# X1.net
KiCad netlist of a schematic drawn in Altium Designer
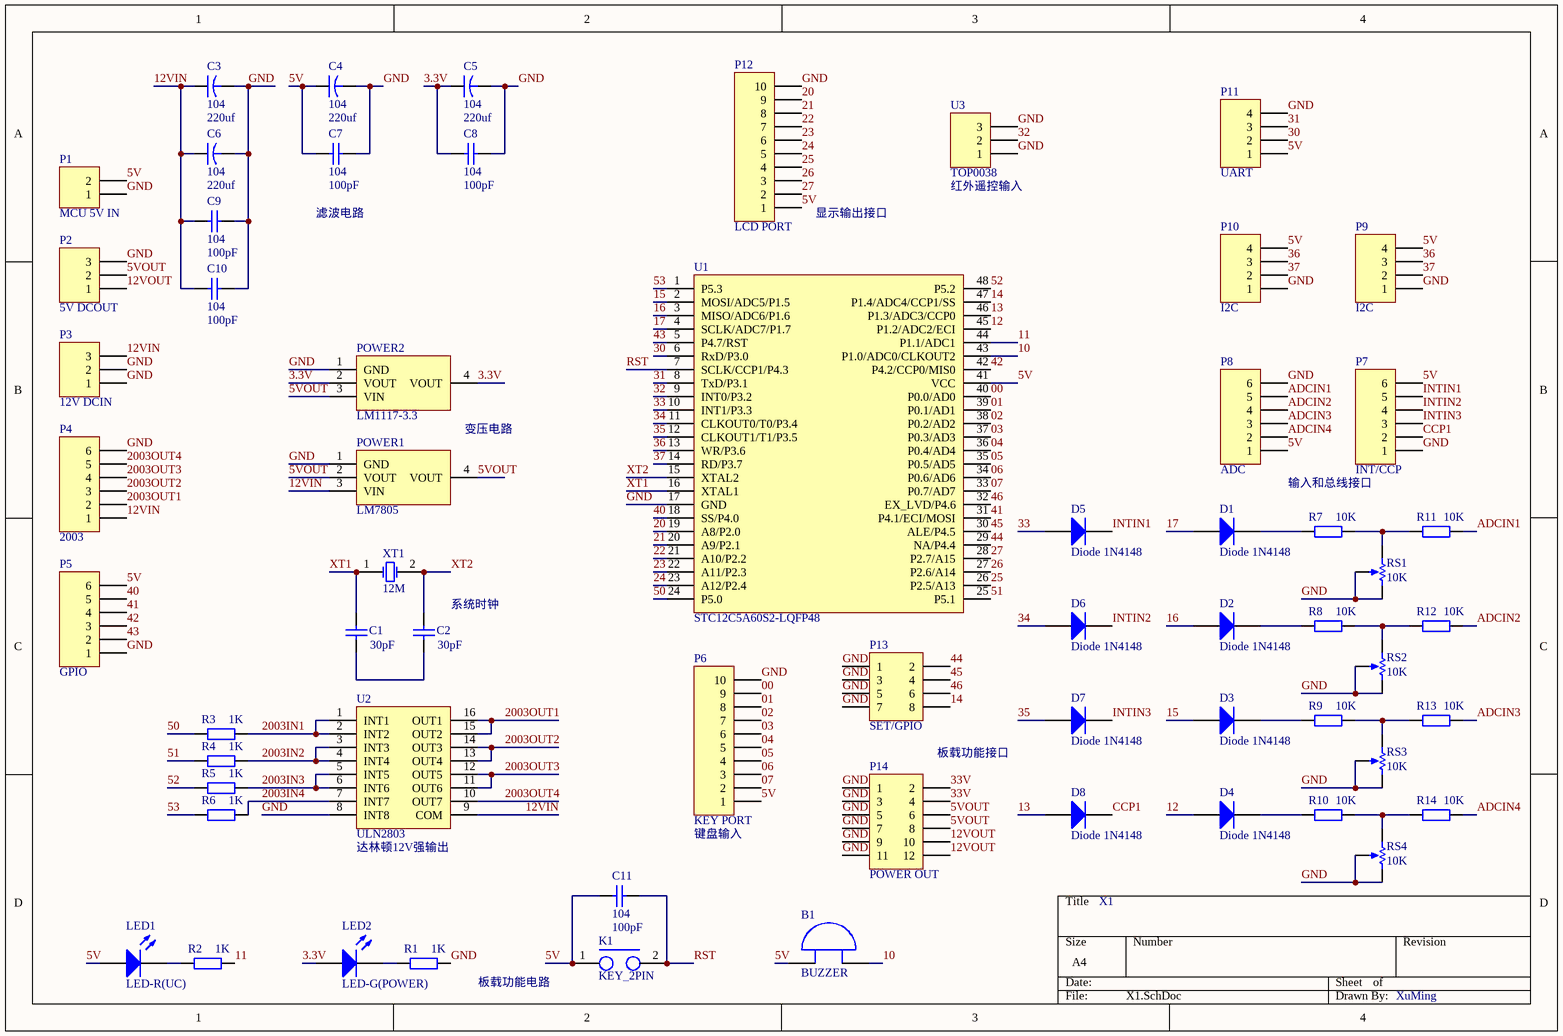
[diagram p0: X1.SchDoc]

(export (version "E")
  (design (tool "Eeschema 10.0.6"))
  (components
    (comp (ref "B1") (value "BUZZER") (footprint "BEEP1") (libsource (lib "X1") (part "BUZZER")))
    (comp (ref "C1")
      (value "30pF")
      (footprint "0805")
      (description "Capacitor")
      (fields (field (name "Comment") "Cap") (field (name "PUBLISHER") "Altium Limited"))
      (libsource (lib "Miscellaneous Devices") (part "Cap"))
    )
    (comp (ref "C2")
      (value "30pF")
      (footprint "0805")
      (description "Capacitor")
      (fields (field (name "Comment") "Cap") (field (name "PUBLISHER") "Altium Limited"))
      (libsource (lib "Miscellaneous Devices") (part "Cap"))
    )
    (comp (ref "C3")
      (value "104")
      (footprint "C107V")
      (description "Capacitor")
      (fields (field (name "ALTIUM_VALUE") "220uf") (field (name "PUBLISHER") "Altium Limited"))
      (libsource (lib "Miscellaneous Devices") (part "Cap2"))
    )
    (comp (ref "C4")
      (value "104")
      (footprint "C107V")
      (description "Capacitor")
      (fields (field (name "ALTIUM_VALUE") "220uf") (field (name "PUBLISHER") "Altium Limited"))
      (libsource (lib "Miscellaneous Devices") (part "Cap2"))
    )
    (comp (ref "C5")
      (value "104")
      (footprint "C107V")
      (description "Capacitor")
      (fields (field (name "ALTIUM_VALUE") "220uf") (field (name "PUBLISHER") "Altium Limited"))
      (libsource (lib "Miscellaneous Devices") (part "Cap2"))
    )
    (comp (ref "C6")
      (value "104")
      (footprint "C107V")
      (description "Capacitor")
      (fields (field (name "ALTIUM_VALUE") "220uf") (field (name "PUBLISHER") "Altium Limited"))
      (libsource (lib "Miscellaneous Devices") (part "Cap2"))
    )
    (comp (ref "C7")
      (value "104")
      (footprint "0805")
      (description "Capacitor")
      (fields (field (name "ALTIUM_VALUE") "100pF") (field (name "PUBLISHER") "Altium Limited"))
      (libsource (lib "Miscellaneous Devices") (part "Cap"))
    )
    (comp (ref "C8")
      (value "104")
      (footprint "0805")
      (description "Capacitor")
      (fields (field (name "ALTIUM_VALUE") "100pF") (field (name "PUBLISHER") "Altium Limited"))
      (libsource (lib "Miscellaneous Devices") (part "Cap"))
    )
    (comp (ref "C9")
      (value "104")
      (footprint "0805")
      (description "Capacitor")
      (fields (field (name "ALTIUM_VALUE") "100pF") (field (name "PUBLISHER") "Altium Limited"))
      (libsource (lib "Miscellaneous Devices") (part "Cap"))
    )
    (comp (ref "C10")
      (value "104")
      (footprint "0805")
      (description "Capacitor")
      (fields (field (name "ALTIUM_VALUE") "100pF") (field (name "PUBLISHER") "Altium Limited"))
      (libsource (lib "Miscellaneous Devices") (part "Cap"))
    )
    (comp (ref "C11")
      (value "104")
      (footprint "0805")
      (description "Capacitor")
      (fields (field (name "ALTIUM_VALUE") "100pF") (field (name "PUBLISHER") "Altium Limited"))
      (libsource (lib "Miscellaneous Devices") (part "Cap"))
    )
    (comp (ref "D1")
      (value "Diode 1N4148")
      (footprint "0805")
      (description "High Conductance Fast Diode")
      (fields (field (name "PUBLISHER") "Altium Limited"))
      (libsource (lib "Miscellaneous Devices") (part "Diode 1N4148"))
    )
    (comp (ref "D2")
      (value "Diode 1N4148")
      (footprint "0805")
      (description "High Conductance Fast Diode")
      (fields (field (name "PUBLISHER") "Altium Limited"))
      (libsource (lib "Miscellaneous Devices") (part "Diode 1N4148"))
    )
    (comp (ref "D3")
      (value "Diode 1N4148")
      (footprint "0805")
      (description "High Conductance Fast Diode")
      (fields (field (name "PUBLISHER") "Altium Limited"))
      (libsource (lib "Miscellaneous Devices") (part "Diode 1N4148"))
    )
    (comp (ref "D4")
      (value "Diode 1N4148")
      (footprint "0805")
      (description "High Conductance Fast Diode")
      (fields (field (name "PUBLISHER") "Altium Limited"))
      (libsource (lib "Miscellaneous Devices") (part "Diode 1N4148"))
    )
    (comp (ref "D5")
      (value "Diode 1N4148")
      (footprint "0805")
      (description "High Conductance Fast Diode")
      (fields (field (name "PUBLISHER") "Altium Limited"))
      (libsource (lib "Miscellaneous Devices") (part "Diode 1N4148"))
    )
    (comp (ref "D6")
      (value "Diode 1N4148")
      (footprint "0805")
      (description "High Conductance Fast Diode")
      (fields (field (name "PUBLISHER") "Altium Limited"))
      (libsource (lib "Miscellaneous Devices") (part "Diode 1N4148"))
    )
    (comp (ref "D7")
      (value "Diode 1N4148")
      (footprint "0805")
      (description "High Conductance Fast Diode")
      (fields (field (name "PUBLISHER") "Altium Limited"))
      (libsource (lib "Miscellaneous Devices") (part "Diode 1N4148"))
    )
    (comp (ref "D8")
      (value "Diode 1N4148")
      (footprint "0805")
      (description "High Conductance Fast Diode")
      (fields (field (name "PUBLISHER") "Altium Limited"))
      (libsource (lib "Miscellaneous Devices") (part "Diode 1N4148"))
    )
    (comp (ref "K1") (value "KEY_2PIN") (footprint "KEY-4Pin") (libsource (lib "X1") (part "KEY_2PIN")))
    (comp (ref "LED1")
      (value "LED-R(UC)")
      (footprint "0805")
      (description "Typical RED, GREEN, YELLOW, AMBER GaAs LED")
      (fields (field (name "PUBLISHER") "Altium Limited"))
      (libsource (lib "Miscellaneous Devices") (part "LED2"))
    )
    (comp (ref "LED2")
      (value "LED-G(POWER)")
      (footprint "0805")
      (description "Typical RED, GREEN, YELLOW, AMBER GaAs LED")
      (fields (field (name "PUBLISHER") "Altium Limited"))
      (libsource (lib "Miscellaneous Devices") (part "LED2"))
    )
    (comp (ref "P1")
      (value "MCU 5V IN")
      (footprint "HDR1X2")
      (description "Header, 2-Pin")
      (fields (field (name "PUBLISHER") "Altium Limited"))
      (libsource (lib "Miscellaneous Connectors") (part "Header 2"))
    )
    (comp (ref "P2")
      (value "5V DCOUT")
      (footprint "HDR1X3")
      (description "Header, 3-Pin")
      (fields (field (name "PUBLISHER") "Altium Limited"))
      (libsource (lib "Miscellaneous Connectors") (part "Header 3"))
    )
    (comp (ref "P3")
      (value "12V DCIN")
      (footprint "HDR1X3")
      (description "Header, 3-Pin")
      (fields (field (name "PUBLISHER") "Altium Limited"))
      (libsource (lib "Miscellaneous Connectors") (part "Header 3"))
    )
    (comp (ref "P4")
      (value "2003")
      (footprint "HDR1X6")
      (description "Header, 6-Pin")
      (fields (field (name "PUBLISHER") "Altium Limited"))
      (libsource (lib "Miscellaneous Connectors") (part "Header 6"))
    )
    (comp (ref "P5")
      (value "GPIO")
      (footprint "HDR1X6")
      (description "Header, 6-Pin")
      (fields (field (name "PUBLISHER") "Altium Limited"))
      (libsource (lib "Miscellaneous Connectors") (part "Header 6"))
    )
    (comp (ref "P6")
      (value "KEY PORT")
      (footprint "HDR1X10")
      (description "Header, 10-Pin")
      (fields (field (name "PUBLISHER") "Altium Limited"))
      (libsource (lib "Miscellaneous Connectors") (part "Header 10"))
    )
    (comp (ref "P7")
      (value "INT/CCP")
      (footprint "HDR1X6")
      (description "Header, 6-Pin")
      (fields (field (name "PUBLISHER") "Altium Limited"))
      (libsource (lib "Miscellaneous Connectors") (part "Header 6"))
    )
    (comp (ref "P8")
      (value "ADC")
      (footprint "HDR1X6")
      (description "Header, 6-Pin")
      (fields (field (name "PUBLISHER") "Altium Limited"))
      (libsource (lib "Miscellaneous Connectors") (part "Header 6"))
    )
    (comp (ref "P9")
      (value "I2C")
      (footprint "HDR1X4")
      (description "Header, 4-Pin")
      (fields (field (name "PUBLISHER") "Altium Limited"))
      (libsource (lib "Miscellaneous Connectors") (part "Header 4"))
    )
    (comp (ref "P10")
      (value "I2C")
      (footprint "HDR1X4")
      (description "Header, 4-Pin")
      (fields (field (name "PUBLISHER") "Altium Limited"))
      (libsource (lib "Miscellaneous Connectors") (part "Header 4"))
    )
    (comp (ref "P11")
      (value "UART")
      (footprint "HDR1X4")
      (description "Header, 4-Pin")
      (fields (field (name "PUBLISHER") "Altium Limited"))
      (libsource (lib "Miscellaneous Connectors") (part "Header 4"))
    )
    (comp (ref "P12")
      (value "LCD PORT")
      (footprint "HDR1X10")
      (description "Header, 10-Pin")
      (fields (field (name "PUBLISHER") "Altium Limited"))
      (libsource (lib "Miscellaneous Connectors") (part "Header 10"))
    )
    (comp (ref "P13")
      (value "SET/GPIO")
      (footprint "HDR2X4")
      (description "Header, 4-Pin, Dual row")
      (fields (field (name "PUBLISHER") "Altium Limited"))
      (libsource (lib "Miscellaneous Connectors") (part "Header 4X2"))
    )
    (comp (ref "P14")
      (value "POWER OUT")
      (footprint "HDR2X6")
      (description "Header, 6-Pin, Dual row")
      (fields (field (name "PUBLISHER") "Altium Limited"))
      (libsource (lib "Miscellaneous Connectors") (part "Header 6X2"))
    )
    (comp (ref "POWER1") (value "LM7805") (footprint "SOT223_N") (libsource (lib "X1") (part "LM7805")))
    (comp (ref "POWER2") (value "LM1117-3.3") (footprint "SOT223_N") (libsource (lib "X1") (part "LM7805")))
    (comp (ref "R1")
      (value "1K")
      (footprint "0805")
      (description "Resistor")
      (fields (field (name "Comment") "Res2") (field (name "PUBLISHER") "Altium Limited"))
      (libsource (lib "Miscellaneous Devices") (part "Res2"))
    )
    (comp (ref "R2")
      (value "1K")
      (footprint "0805")
      (description "Resistor")
      (fields (field (name "Comment") "Res2") (field (name "PUBLISHER") "Altium Limited"))
      (libsource (lib "Miscellaneous Devices") (part "Res2"))
    )
    (comp (ref "R3")
      (value "1K")
      (footprint "0805")
      (description "Resistor")
      (fields (field (name "Comment") "Res2") (field (name "PUBLISHER") "Altium Limited"))
      (libsource (lib "Miscellaneous Devices") (part "Res2"))
    )
    (comp (ref "R4")
      (value "1K")
      (footprint "0805")
      (description "Resistor")
      (fields (field (name "Comment") "Res2") (field (name "PUBLISHER") "Altium Limited"))
      (libsource (lib "Miscellaneous Devices") (part "Res2"))
    )
    (comp (ref "R5")
      (value "1K")
      (footprint "0805")
      (description "Resistor")
      (fields (field (name "Comment") "Res2") (field (name "PUBLISHER") "Altium Limited"))
      (libsource (lib "Miscellaneous Devices") (part "Res2"))
    )
    (comp (ref "R6")
      (value "1K")
      (footprint "0805")
      (description "Resistor")
      (fields (field (name "Comment") "Res2") (field (name "PUBLISHER") "Altium Limited"))
      (libsource (lib "Miscellaneous Devices") (part "Res2"))
    )
    (comp (ref "R7")
      (value "10K")
      (footprint "0805")
      (description "Resistor")
      (fields (field (name "Comment") "Res2") (field (name "PUBLISHER") "Altium Limited"))
      (libsource (lib "Miscellaneous Devices") (part "Res2"))
    )
    (comp (ref "R8")
      (value "10K")
      (footprint "0805")
      (description "Resistor")
      (fields (field (name "Comment") "Res2") (field (name "PUBLISHER") "Altium Limited"))
      (libsource (lib "Miscellaneous Devices") (part "Res2"))
    )
    (comp (ref "R9")
      (value "10K")
      (footprint "0805")
      (description "Resistor")
      (fields (field (name "Comment") "Res2") (field (name "PUBLISHER") "Altium Limited"))
      (libsource (lib "Miscellaneous Devices") (part "Res2"))
    )
    (comp (ref "R10")
      (value "10K")
      (footprint "0805")
      (description "Resistor")
      (fields (field (name "Comment") "Res2") (field (name "PUBLISHER") "Altium Limited"))
      (libsource (lib "Miscellaneous Devices") (part "Res2"))
    )
    (comp (ref "R11")
      (value "10K")
      (footprint "0805")
      (description "Resistor")
      (fields (field (name "Comment") "Res2") (field (name "PUBLISHER") "Altium Limited"))
      (libsource (lib "Miscellaneous Devices") (part "Res2"))
    )
    (comp (ref "R12")
      (value "10K")
      (footprint "0805")
      (description "Resistor")
      (fields (field (name "Comment") "Res2") (field (name "PUBLISHER") "Altium Limited"))
      (libsource (lib "Miscellaneous Devices") (part "Res2"))
    )
    (comp (ref "R13")
      (value "10K")
      (footprint "0805")
      (description "Resistor")
      (fields (field (name "Comment") "Res2") (field (name "PUBLISHER") "Altium Limited"))
      (libsource (lib "Miscellaneous Devices") (part "Res2"))
    )
    (comp (ref "R14")
      (value "10K")
      (footprint "0805")
      (description "Resistor")
      (fields (field (name "Comment") "Res2") (field (name "PUBLISHER") "Altium Limited"))
      (libsource (lib "Miscellaneous Devices") (part "Res2"))
    )
    (comp (ref "RS1")
      (value "10K")
      (footprint "VR5")
      (description "Potentiometer")
      (fields (field (name "Comment") "RPot") (field (name "PUBLISHER") "Altium Limited"))
      (libsource (lib "Miscellaneous Devices") (part "RPot"))
    )
    (comp (ref "RS2")
      (value "10K")
      (footprint "VR5")
      (description "Potentiometer")
      (fields (field (name "Comment") "RPot") (field (name "PUBLISHER") "Altium Limited"))
      (libsource (lib "Miscellaneous Devices") (part "RPot"))
    )
    (comp (ref "RS3")
      (value "10K")
      (footprint "VR5")
      (description "Potentiometer")
      (fields (field (name "Comment") "RPot") (field (name "PUBLISHER") "Altium Limited"))
      (libsource (lib "Miscellaneous Devices") (part "RPot"))
    )
    (comp (ref "RS4")
      (value "10K")
      (footprint "VR5")
      (description "Potentiometer")
      (fields (field (name "Comment") "RPot") (field (name "PUBLISHER") "Altium Limited"))
      (libsource (lib "Miscellaneous Devices") (part "RPot"))
    )
    (comp (ref "U1")
      (value "STC12C5A60S2-LQFP48")
      (footprint "LQFP-48_7x7x05P")
      (libsource (lib "X1") (part "STC12C5A60S2-LQFP48"))
    )
    (comp (ref "U2") (value "ULN2803") (footprint "SOP-16") (libsource (lib "Schlib1") (part "ULN2003")))
    (comp (ref "U3")
      (value "TOP0038")
      (footprint "HDR1X3")
      (description "Header, 3-Pin")
      (fields (field (name "PUBLISHER") "Altium Limited"))
      (libsource (lib "Miscellaneous Connectors") (part "Header 3"))
    )
    (comp (ref "XT1")
      (value "12M")
      (footprint "R38")
      (description "Crystal Oscillator")
      (fields (field (name "PUBLISHER") "Altium Limited"))
      (libsource (lib "Miscellaneous Devices") (part "XTAL"))
    )
  )
  (nets
    (net (code "1") (name "/00") (class "Default")
      (node (ref "P6") (pin "9") (pinfunction "9_9") (pintype "passive"))
      (node (ref "U1") (pin "40") (pinfunction "P0.0/AD0_40") (pintype "passive"))
    )
    (net (code "2") (name "/01") (class "Default")
      (node (ref "P6") (pin "8") (pinfunction "8_8") (pintype "passive"))
      (node (ref "U1") (pin "39") (pinfunction "P0.1/AD1_39") (pintype "passive"))
    )
    (net (code "3") (name "/02") (class "Default")
      (node (ref "P6") (pin "7") (pinfunction "7_7") (pintype "passive"))
      (node (ref "U1") (pin "38") (pinfunction "P0.2/AD2_38") (pintype "passive"))
    )
    (net (code "4") (name "/03") (class "Default")
      (node (ref "P6") (pin "6") (pinfunction "6_6") (pintype "passive"))
      (node (ref "U1") (pin "37") (pinfunction "P0.3/AD3_37") (pintype "passive"))
    )
    (net (code "5") (name "/3.3V") (class "Default")
      (node (ref "C5") (pin "1") (pinfunction "1_1") (pintype "passive"))
      (node (ref "C8") (pin "1") (pinfunction "1_1") (pintype "passive"))
      (node (ref "LED2") (pin "1") (pinfunction "A_1") (pintype "passive"))
      (node (ref "POWER2") (pin "2") (pinfunction "VOUT_2") (pintype "passive"))
      (node (ref "POWER2") (pin "4") (pinfunction "VOUT_4") (pintype "passive"))
    )
    (net (code "6") (name "/04") (class "Default")
      (node (ref "P6") (pin "5") (pinfunction "5_5") (pintype "passive"))
      (node (ref "U1") (pin "36") (pinfunction "P0.4/AD4_36") (pintype "passive"))
    )
    (net (code "7") (name "/05") (class "Default")
      (node (ref "P6") (pin "4") (pinfunction "4_4") (pintype "passive"))
      (node (ref "U1") (pin "35") (pinfunction "P0.5/AD5_35") (pintype "passive"))
    )
    (net (code "8") (name "/5V") (class "Default")
      (node (ref "B1") (pin "1") (pinfunction "1_1") (pintype "passive"))
      (node (ref "C11") (pin "1") (pinfunction "1_1") (pintype "passive"))
      (node (ref "C4") (pin "1") (pinfunction "1_1") (pintype "passive"))
      (node (ref "C7") (pin "1") (pinfunction "1_1") (pintype "passive"))
      (node (ref "K1") (pin "1") (pinfunction "1_1") (pintype "passive"))
      (node (ref "LED1") (pin "1") (pinfunction "A_1") (pintype "passive"))
      (node (ref "P1") (pin "2") (pinfunction "2_2") (pintype "passive"))
      (node (ref "P10") (pin "4") (pinfunction "4_4") (pintype "passive"))
      (node (ref "P11") (pin "1") (pinfunction "1_1") (pintype "passive"))
      (node (ref "P12") (pin "1") (pinfunction "1_1") (pintype "passive"))
      (node (ref "P5") (pin "6") (pinfunction "6_6") (pintype "passive"))
      (node (ref "P6") (pin "1") (pinfunction "1_1") (pintype "passive"))
      (node (ref "P7") (pin "6") (pinfunction "6_6") (pintype "passive"))
      (node (ref "P8") (pin "1") (pinfunction "1_1") (pintype "passive"))
      (node (ref "P9") (pin "4") (pinfunction "4_4") (pintype "passive"))
      (node (ref "U1") (pin "41") (pinfunction "VCC_41") (pintype "passive"))
    )
    (net (code "9") (name "/5VOUT") (class "Default")
      (node (ref "P14") (pin "6") (pinfunction "6_6") (pintype "passive"))
      (node (ref "P14") (pin "8") (pinfunction "8_8") (pintype "passive"))
      (node (ref "P2") (pin "2") (pinfunction "2_2") (pintype "passive"))
      (node (ref "POWER1") (pin "2") (pinfunction "VOUT_2") (pintype "passive"))
      (node (ref "POWER1") (pin "4") (pinfunction "VOUT_4") (pintype "passive"))
      (node (ref "POWER2") (pin "3") (pinfunction "VIN_3") (pintype "passive"))
    )
    (net (code "10") (name "/06") (class "Default")
      (node (ref "P6") (pin "3") (pinfunction "3_3") (pintype "passive"))
      (node (ref "U1") (pin "34") (pinfunction "P0.6/AD6_34") (pintype "passive"))
    )
    (net (code "11") (name "/07") (class "Default")
      (node (ref "P6") (pin "2") (pinfunction "2_2") (pintype "passive"))
      (node (ref "U1") (pin "33") (pinfunction "P0.7/AD7_33") (pintype "passive"))
    )
    (net (code "12") (name "/10") (class "Default")
      (node (ref "B1") (pin "2") (pinfunction "2_2") (pintype "passive"))
      (node (ref "U1") (pin "43") (pinfunction "P1.0/ADC0/CLKOUT2_43") (pintype "passive"))
    )
    (net (code "13") (name "/11") (class "Default")
      (node (ref "R2") (pin "2") (pinfunction "2_2") (pintype "passive"))
      (node (ref "U1") (pin "44") (pinfunction "P1.1/ADC1_44") (pintype "passive"))
    )
    (net (code "14") (name "/12") (class "Default")
      (node (ref "D4") (pin "1") (pinfunction "A_1") (pintype "passive"))
      (node (ref "U1") (pin "45") (pinfunction "P1.2/ADC2/ECI_45") (pintype "passive"))
    )
    (net (code "15") (name "/12VIN") (class "Default")
      (node (ref "C10") (pin "1") (pinfunction "1_1") (pintype "passive"))
      (node (ref "C3") (pin "1") (pinfunction "1_1") (pintype "passive"))
      (node (ref "C6") (pin "1") (pinfunction "1_1") (pintype "passive"))
      (node (ref "C9") (pin "1") (pinfunction "1_1") (pintype "passive"))
      (node (ref "P3") (pin "3") (pinfunction "3_3") (pintype "passive"))
      (node (ref "P4") (pin "1") (pinfunction "1_1") (pintype "passive"))
      (node (ref "POWER1") (pin "3") (pinfunction "VIN_3") (pintype "passive"))
      (node (ref "U2") (pin "9") (pinfunction "COM_9") (pintype "passive"))
    )
    (net (code "16") (name "/12VOUT") (class "Default")
      (node (ref "P14") (pin "10") (pinfunction "10_10") (pintype "passive"))
      (node (ref "P14") (pin "12") (pinfunction "12_12") (pintype "passive"))
      (node (ref "P2") (pin "1") (pinfunction "1_1") (pintype "passive"))
    )
    (net (code "17") (name "/13") (class "Default")
      (node (ref "D8") (pin "1") (pinfunction "A_1") (pintype "passive"))
      (node (ref "U1") (pin "46") (pinfunction "P1.3/ADC3/CCP0_46") (pintype "passive"))
    )
    (net (code "18") (name "/14") (class "Default")
      (node (ref "P13") (pin "8") (pinfunction "8_8") (pintype "passive"))
      (node (ref "U1") (pin "47") (pinfunction "P1.4/ADC4/CCP1/SS_47") (pintype "passive"))
    )
    (net (code "19") (name "/15") (class "Default")
      (node (ref "D3") (pin "1") (pinfunction "A_1") (pintype "passive"))
      (node (ref "U1") (pin "2") (pinfunction "MOSI/ADC5/P1.5_2") (pintype "passive"))
    )
    (net (code "20") (name "/16") (class "Default")
      (node (ref "D2") (pin "1") (pinfunction "A_1") (pintype "passive"))
      (node (ref "U1") (pin "3") (pinfunction "MISO/ADC6/P1.6_3") (pintype "passive"))
    )
    (net (code "21") (name "/17") (class "Default")
      (node (ref "D1") (pin "1") (pinfunction "A_1") (pintype "passive"))
      (node (ref "U1") (pin "4") (pinfunction "SCLK/ADC7/P1.7_4") (pintype "passive"))
    )
    (net (code "22") (name "/20") (class "Default")
      (node (ref "P12") (pin "9") (pinfunction "9_9") (pintype "passive"))
      (node (ref "U1") (pin "19") (pinfunction "A8/P2.0_19") (pintype "passive"))
    )
    (net (code "23") (name "/21") (class "Default")
      (node (ref "P12") (pin "8") (pinfunction "8_8") (pintype "passive"))
      (node (ref "U1") (pin "20") (pinfunction "A9/P2.1_20") (pintype "passive"))
    )
    (net (code "24") (name "/22") (class "Default")
      (node (ref "P12") (pin "7") (pinfunction "7_7") (pintype "passive"))
      (node (ref "U1") (pin "21") (pinfunction "A10/P2.2_21") (pintype "passive"))
    )
    (net (code "25") (name "/23") (class "Default")
      (node (ref "P12") (pin "6") (pinfunction "6_6") (pintype "passive"))
      (node (ref "U1") (pin "22") (pinfunction "A11/P2.3_22") (pintype "passive"))
    )
    (net (code "26") (name "/24") (class "Default")
      (node (ref "P12") (pin "5") (pinfunction "5_5") (pintype "passive"))
      (node (ref "U1") (pin "23") (pinfunction "A12/P2.4_23") (pintype "passive"))
    )
    (net (code "27") (name "/25") (class "Default")
      (node (ref "P12") (pin "4") (pinfunction "4_4") (pintype "passive"))
      (node (ref "U1") (pin "26") (pinfunction "P2.5/A13_26") (pintype "passive"))
    )
    (net (code "28") (name "/26") (class "Default")
      (node (ref "P12") (pin "3") (pinfunction "3_3") (pintype "passive"))
      (node (ref "U1") (pin "27") (pinfunction "P2.6/A14_27") (pintype "passive"))
    )
    (net (code "29") (name "/27") (class "Default")
      (node (ref "P12") (pin "2") (pinfunction "2_2") (pintype "passive"))
      (node (ref "U1") (pin "28") (pinfunction "P2.7/A15_28") (pintype "passive"))
    )
    (net (code "30") (name "/30") (class "Default")
      (node (ref "P11") (pin "2") (pinfunction "2_2") (pintype "passive"))
      (node (ref "U1") (pin "6") (pinfunction "RxD/P3.0_6") (pintype "passive"))
    )
    (net (code "31") (name "/31") (class "Default")
      (node (ref "P11") (pin "3") (pinfunction "3_3") (pintype "passive"))
      (node (ref "U1") (pin "8") (pinfunction "TxD/P3.1_8") (pintype "passive"))
    )
    (net (code "32") (name "/32") (class "Default")
      (node (ref "U1") (pin "9") (pinfunction "INT0/P3.2_9") (pintype "passive"))
      (node (ref "U3") (pin "2") (pinfunction "2_2") (pintype "passive"))
    )
    (net (code "33") (name "/33") (class "Default")
      (node (ref "D5") (pin "1") (pinfunction "A_1") (pintype "passive"))
      (node (ref "U1") (pin "10") (pinfunction "INT1/P3.3_10") (pintype "passive"))
    )
    (net (code "34") (name "/33V") (class "Default")
      (node (ref "P14") (pin "2") (pinfunction "2_2") (pintype "passive"))
      (node (ref "P14") (pin "4") (pinfunction "4_4") (pintype "passive"))
    )
    (net (code "35") (name "/34") (class "Default")
      (node (ref "D6") (pin "1") (pinfunction "A_1") (pintype "passive"))
      (node (ref "U1") (pin "11") (pinfunction "CLKOUT0/T0/P3.4_11") (pintype "passive"))
    )
    (net (code "36") (name "/35") (class "Default")
      (node (ref "D7") (pin "1") (pinfunction "A_1") (pintype "passive"))
      (node (ref "U1") (pin "12") (pinfunction "CLKOUT1/T1/P3.5_12") (pintype "passive"))
    )
    (net (code "37") (name "/36") (class "Default")
      (node (ref "P10") (pin "3") (pinfunction "3_3") (pintype "passive"))
      (node (ref "P9") (pin "3") (pinfunction "3_3") (pintype "passive"))
      (node (ref "U1") (pin "13") (pinfunction "WR/P3.6_13") (pintype "passive"))
    )
    (net (code "38") (name "/37") (class "Default")
      (node (ref "P10") (pin "2") (pinfunction "2_2") (pintype "passive"))
      (node (ref "P9") (pin "2") (pinfunction "2_2") (pintype "passive"))
      (node (ref "U1") (pin "14") (pinfunction "RD/P3.7_14") (pintype "passive"))
    )
    (net (code "39") (name "/40") (class "Default")
      (node (ref "P5") (pin "5") (pinfunction "5_5") (pintype "passive"))
      (node (ref "U1") (pin "18") (pinfunction "SS/P4.0_18") (pintype "passive"))
    )
    (net (code "40") (name "/41") (class "Default")
      (node (ref "P5") (pin "4") (pinfunction "4_4") (pintype "passive"))
      (node (ref "U1") (pin "31") (pinfunction "P4.1/ECI/MOSI_31") (pintype "passive"))
    )
    (net (code "41") (name "/42") (class "Default")
      (node (ref "P5") (pin "3") (pinfunction "3_3") (pintype "passive"))
      (node (ref "U1") (pin "42") (pinfunction "P4.2/CCP0/MIS0_42") (pintype "passive"))
    )
    (net (code "42") (name "/43") (class "Default")
      (node (ref "P5") (pin "2") (pinfunction "2_2") (pintype "passive"))
      (node (ref "U1") (pin "5") (pinfunction "P4.7/RST_5") (pintype "passive"))
    )
    (net (code "43") (name "/44") (class "Default")
      (node (ref "P13") (pin "2") (pinfunction "2_2") (pintype "passive"))
      (node (ref "U1") (pin "29") (pinfunction "NA/P4.4_29") (pintype "passive"))
    )
    (net (code "44") (name "/45") (class "Default")
      (node (ref "P13") (pin "4") (pinfunction "4_4") (pintype "passive"))
      (node (ref "U1") (pin "30") (pinfunction "ALE/P4.5_30") (pintype "passive"))
    )
    (net (code "45") (name "/46") (class "Default")
      (node (ref "P13") (pin "6") (pinfunction "6_6") (pintype "passive"))
      (node (ref "U1") (pin "32") (pinfunction "EX_LVD/P4.6_32") (pintype "passive"))
    )
    (net (code "46") (name "/50") (class "Default")
      (node (ref "R3") (pin "1") (pinfunction "1_1") (pintype "passive"))
      (node (ref "U1") (pin "24") (pinfunction "P5.0_24") (pintype "passive"))
    )
    (net (code "47") (name "/51") (class "Default")
      (node (ref "R4") (pin "1") (pinfunction "1_1") (pintype "passive"))
      (node (ref "U1") (pin "25") (pinfunction "P5.1_25") (pintype "passive"))
    )
    (net (code "48") (name "/52") (class "Default")
      (node (ref "R5") (pin "1") (pinfunction "1_1") (pintype "passive"))
      (node (ref "U1") (pin "48") (pinfunction "P5.2_48") (pintype "passive"))
    )
    (net (code "49") (name "/53") (class "Default")
      (node (ref "R6") (pin "1") (pinfunction "1_1") (pintype "passive"))
      (node (ref "U1") (pin "1") (pinfunction "P5.3_1") (pintype "passive"))
    )
    (net (code "50") (name "/2003IN1") (class "Default")
      (node (ref "R3") (pin "2") (pinfunction "2_2") (pintype "passive"))
      (node (ref "U2") (pin "1") (pinfunction "INT1_1") (pintype "passive"))
      (node (ref "U2") (pin "2") (pinfunction "INT2_2") (pintype "passive"))
    )
    (net (code "51") (name "/2003IN2") (class "Default")
      (node (ref "R4") (pin "2") (pinfunction "2_2") (pintype "passive"))
      (node (ref "U2") (pin "3") (pinfunction "INT3_3") (pintype "passive"))
      (node (ref "U2") (pin "4") (pinfunction "INT4_4") (pintype "passive"))
    )
    (net (code "52") (name "/2003IN3") (class "Default")
      (node (ref "R5") (pin "2") (pinfunction "2_2") (pintype "passive"))
      (node (ref "U2") (pin "5") (pinfunction "INT5_5") (pintype "passive"))
      (node (ref "U2") (pin "6") (pinfunction "INT6_6") (pintype "passive"))
    )
    (net (code "53") (name "/2003IN4") (class "Default")
      (node (ref "R6") (pin "2") (pinfunction "2_2") (pintype "passive"))
      (node (ref "U2") (pin "7") (pinfunction "INT7_7") (pintype "passive"))
    )
    (net (code "54") (name "/2003OUT1") (class "Default")
      (node (ref "P4") (pin "2") (pinfunction "2_2") (pintype "passive"))
      (node (ref "U2") (pin "15") (pinfunction "OUT2_15") (pintype "passive"))
      (node (ref "U2") (pin "16") (pinfunction "OUT1_16") (pintype "passive"))
    )
    (net (code "55") (name "/2003OUT2") (class "Default")
      (node (ref "P4") (pin "3") (pinfunction "3_3") (pintype "passive"))
      (node (ref "U2") (pin "13") (pinfunction "OUT4_13") (pintype "passive"))
      (node (ref "U2") (pin "14") (pinfunction "OUT3_14") (pintype "passive"))
    )
    (net (code "56") (name "/2003OUT3") (class "Default")
      (node (ref "P4") (pin "4") (pinfunction "4_4") (pintype "passive"))
      (node (ref "U2") (pin "11") (pinfunction "OUT6_11") (pintype "passive"))
      (node (ref "U2") (pin "12") (pinfunction "OUT5_12") (pintype "passive"))
    )
    (net (code "57") (name "/2003OUT4") (class "Default")
      (node (ref "P4") (pin "5") (pinfunction "5_5") (pintype "passive"))
      (node (ref "U2") (pin "10") (pinfunction "OUT7_10") (pintype "passive"))
    )
    (net (code "58") (name "/ADCIN1") (class "Default")
      (node (ref "P8") (pin "5") (pinfunction "5_5") (pintype "passive"))
      (node (ref "R11") (pin "2") (pinfunction "2_2") (pintype "passive"))
    )
    (net (code "59") (name "/ADCIN2") (class "Default")
      (node (ref "P8") (pin "4") (pinfunction "4_4") (pintype "passive"))
      (node (ref "R12") (pin "2") (pinfunction "2_2") (pintype "passive"))
    )
    (net (code "60") (name "/ADCIN3") (class "Default")
      (node (ref "P8") (pin "3") (pinfunction "3_3") (pintype "passive"))
      (node (ref "R13") (pin "2") (pinfunction "2_2") (pintype "passive"))
    )
    (net (code "61") (name "/ADCIN4") (class "Default")
      (node (ref "P8") (pin "2") (pinfunction "2_2") (pintype "passive"))
      (node (ref "R14") (pin "2") (pinfunction "2_2") (pintype "passive"))
    )
    (net (code "62") (name "/CCP1") (class "Default")
      (node (ref "D8") (pin "2") (pinfunction "K_2") (pintype "passive"))
      (node (ref "P7") (pin "2") (pinfunction "2_2") (pintype "passive"))
    )
    (net (code "63") (name "/GND") (class "Default")
      (node (ref "C10") (pin "2") (pinfunction "2_2") (pintype "passive"))
      (node (ref "C3") (pin "2") (pinfunction "2_2") (pintype "passive"))
      (node (ref "C4") (pin "2") (pinfunction "2_2") (pintype "passive"))
      (node (ref "C5") (pin "2") (pinfunction "2_2") (pintype "passive"))
      (node (ref "C6") (pin "2") (pinfunction "2_2") (pintype "passive"))
      (node (ref "C7") (pin "2") (pinfunction "2_2") (pintype "passive"))
      (node (ref "C8") (pin "2") (pinfunction "2_2") (pintype "passive"))
      (node (ref "C9") (pin "2") (pinfunction "2_2") (pintype "passive"))
      (node (ref "P1") (pin "1") (pinfunction "1_1") (pintype "passive"))
      (node (ref "P10") (pin "1") (pinfunction "1_1") (pintype "passive"))
      (node (ref "P11") (pin "4") (pinfunction "4_4") (pintype "passive"))
      (node (ref "P12") (pin "10") (pinfunction "10_10") (pintype "passive"))
      (node (ref "P13") (pin "1") (pinfunction "1_1") (pintype "passive"))
      (node (ref "P13") (pin "3") (pinfunction "3_3") (pintype "passive"))
      (node (ref "P13") (pin "5") (pinfunction "5_5") (pintype "passive"))
      (node (ref "P13") (pin "7") (pinfunction "7_7") (pintype "passive"))
      (node (ref "P14") (pin "1") (pinfunction "1_1") (pintype "passive"))
      (node (ref "P14") (pin "11") (pinfunction "11_11") (pintype "passive"))
      (node (ref "P14") (pin "3") (pinfunction "3_3") (pintype "passive"))
      (node (ref "P14") (pin "5") (pinfunction "5_5") (pintype "passive"))
      (node (ref "P14") (pin "7") (pinfunction "7_7") (pintype "passive"))
      (node (ref "P14") (pin "9") (pinfunction "9_9") (pintype "passive"))
      (node (ref "P2") (pin "3") (pinfunction "3_3") (pintype "passive"))
      (node (ref "P3") (pin "1") (pinfunction "1_1") (pintype "passive"))
      (node (ref "P3") (pin "2") (pinfunction "2_2") (pintype "passive"))
      (node (ref "P4") (pin "6") (pinfunction "6_6") (pintype "passive"))
      (node (ref "P5") (pin "1") (pinfunction "1_1") (pintype "passive"))
      (node (ref "P6") (pin "10") (pinfunction "10_10") (pintype "passive"))
      (node (ref "P7") (pin "1") (pinfunction "1_1") (pintype "passive"))
      (node (ref "P8") (pin "6") (pinfunction "6_6") (pintype "passive"))
      (node (ref "P9") (pin "1") (pinfunction "1_1") (pintype "passive"))
      (node (ref "POWER1") (pin "1") (pinfunction "GND_1") (pintype "passive"))
      (node (ref "POWER2") (pin "1") (pinfunction "GND_1") (pintype "passive"))
      (node (ref "R1") (pin "2") (pinfunction "2_2") (pintype "passive"))
      (node (ref "RS1") (pin "2") (pinfunction "BOT_2") (pintype "passive"))
      (node (ref "RS1") (pin "3") (pinfunction "TAP_3") (pintype "passive"))
      (node (ref "RS2") (pin "2") (pinfunction "BOT_2") (pintype "passive"))
      (node (ref "RS2") (pin "3") (pinfunction "TAP_3") (pintype "passive"))
      (node (ref "RS3") (pin "2") (pinfunction "BOT_2") (pintype "passive"))
      (node (ref "RS3") (pin "3") (pinfunction "TAP_3") (pintype "passive"))
      (node (ref "RS4") (pin "2") (pinfunction "BOT_2") (pintype "passive"))
      (node (ref "RS4") (pin "3") (pinfunction "TAP_3") (pintype "passive"))
      (node (ref "U1") (pin "17") (pinfunction "GND_17") (pintype "passive"))
      (node (ref "U2") (pin "8") (pinfunction "INT8_8") (pintype "passive"))
      (node (ref "U3") (pin "1") (pinfunction "1_1") (pintype "passive"))
      (node (ref "U3") (pin "3") (pinfunction "3_3") (pintype "passive"))
    )
    (net (code "64") (name "/INTIN1") (class "Default")
      (node (ref "D5") (pin "2") (pinfunction "K_2") (pintype "passive"))
      (node (ref "P7") (pin "5") (pinfunction "5_5") (pintype "passive"))
    )
    (net (code "65") (name "/INTIN2") (class "Default")
      (node (ref "D6") (pin "2") (pinfunction "K_2") (pintype "passive"))
      (node (ref "P7") (pin "4") (pinfunction "4_4") (pintype "passive"))
    )
    (net (code "66") (name "/INTIN3") (class "Default")
      (node (ref "D7") (pin "2") (pinfunction "K_2") (pintype "passive"))
      (node (ref "P7") (pin "3") (pinfunction "3_3") (pintype "passive"))
    )
    (net (code "67") (name "/RST") (class "Default")
      (node (ref "C11") (pin "2") (pinfunction "2_2") (pintype "passive"))
      (node (ref "K1") (pin "2") (pinfunction "2_2") (pintype "passive"))
      (node (ref "U1") (pin "7") (pinfunction "SCLK/CCP1/P4.3_7") (pintype "passive"))
    )
    (net (code "68") (name "/XT1") (class "Default")
      (node (ref "C1") (pin "2") (pinfunction "2_2") (pintype "passive"))
      (node (ref "U1") (pin "16") (pinfunction "XTAL1_16") (pintype "passive"))
      (node (ref "XT1") (pin "1") (pinfunction "OSC1_1") (pintype "passive"))
    )
    (net (code "69") (name "/XT2") (class "Default")
      (node (ref "C2") (pin "2") (pinfunction "2_2") (pintype "passive"))
      (node (ref "U1") (pin "15") (pinfunction "XTAL2_15") (pintype "passive"))
      (node (ref "XT1") (pin "2") (pinfunction "OSC2_2") (pintype "passive"))
    )
    (net (code "70") (name "Net-(C1-Pad1)") (class "Default")
      (node (ref "C1") (pin "1") (pinfunction "1_1") (pintype "passive"))
      (node (ref "C2") (pin "1") (pinfunction "1_1") (pintype "passive"))
    )
    (net (code "71") (name "Net-(D1-K)") (class "Default")
      (node (ref "D1") (pin "2") (pinfunction "K_2") (pintype "passive"))
      (node (ref "R7") (pin "1") (pinfunction "1_1") (pintype "passive"))
    )
    (net (code "72") (name "Net-(D2-K)") (class "Default")
      (node (ref "D2") (pin "2") (pinfunction "K_2") (pintype "passive"))
      (node (ref "R8") (pin "1") (pinfunction "1_1") (pintype "passive"))
    )
    (net (code "73") (name "Net-(D3-K)") (class "Default")
      (node (ref "D3") (pin "2") (pinfunction "K_2") (pintype "passive"))
      (node (ref "R9") (pin "1") (pinfunction "1_1") (pintype "passive"))
    )
    (net (code "74") (name "Net-(D4-K)") (class "Default")
      (node (ref "D4") (pin "2") (pinfunction "K_2") (pintype "passive"))
      (node (ref "R10") (pin "1") (pinfunction "1_1") (pintype "passive"))
    )
    (net (code "75") (name "Net-(LED1-K)") (class "Default")
      (node (ref "LED1") (pin "2") (pinfunction "K_2") (pintype "passive"))
      (node (ref "R2") (pin "1") (pinfunction "1_1") (pintype "passive"))
    )
    (net (code "76") (name "Net-(LED2-K)") (class "Default")
      (node (ref "LED2") (pin "2") (pinfunction "K_2") (pintype "passive"))
      (node (ref "R1") (pin "1") (pinfunction "1_1") (pintype "passive"))
    )
    (net (code "77") (name "Net-(RS1-TOP)") (class "Default")
      (node (ref "R11") (pin "1") (pinfunction "1_1") (pintype "passive"))
      (node (ref "R7") (pin "2") (pinfunction "2_2") (pintype "passive"))
      (node (ref "RS1") (pin "1") (pinfunction "TOP_1") (pintype "passive"))
    )
    (net (code "78") (name "Net-(RS2-TOP)") (class "Default")
      (node (ref "R12") (pin "1") (pinfunction "1_1") (pintype "passive"))
      (node (ref "R8") (pin "2") (pinfunction "2_2") (pintype "passive"))
      (node (ref "RS2") (pin "1") (pinfunction "TOP_1") (pintype "passive"))
    )
    (net (code "79") (name "Net-(RS3-TOP)") (class "Default")
      (node (ref "R13") (pin "1") (pinfunction "1_1") (pintype "passive"))
      (node (ref "R9") (pin "2") (pinfunction "2_2") (pintype "passive"))
      (node (ref "RS3") (pin "1") (pinfunction "TOP_1") (pintype "passive"))
    )
    (net (code "80") (name "Net-(RS4-TOP)") (class "Default")
      (node (ref "R10") (pin "2") (pinfunction "2_2") (pintype "passive"))
      (node (ref "R14") (pin "1") (pinfunction "1_1") (pintype "passive"))
      (node (ref "RS4") (pin "1") (pinfunction "TOP_1") (pintype "passive"))
    )
  )
)
